# on_off_latch.net
KiCad netlist of a schematic drawn in EAGLE
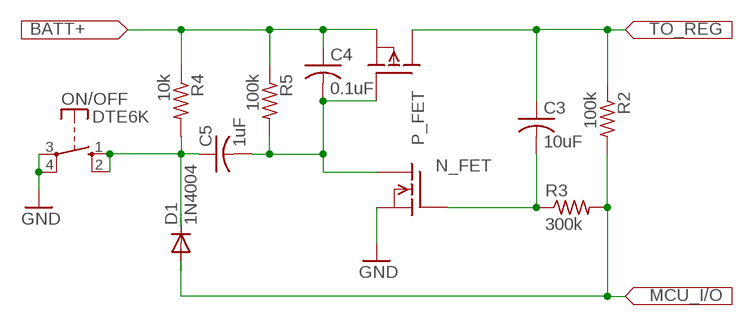
[diagram p0: schematic, sheet 1]

(export (version "E")
  (design (tool "Eeschema 10.0.6"))
  (components
    (comp (ref "C3")
      (value "10uF")
      (footprint "eagle-import:C050-024X044")
      (libsource (lib "eagle-import") (part "C-US050-024X044"))
    )
    (comp (ref "C4")
      (value "0.1uF")
      (footprint "eagle-import:C050-024X044")
      (libsource (lib "eagle-import") (part "C-US050-024X044"))
    )
    (comp (ref "C5")
      (value "1uF")
      (footprint "eagle-import:C050-024X044")
      (libsource (lib "eagle-import") (part "C-US050-024X044"))
    )
    (comp (ref "D1")
      (value "1N4004")
      (footprint "eagle-import:DO41-10")
      (libsource (lib "eagle-import") (part "1N4004"))
    )
    (comp (ref "N_FET")
      (value "BSS101")
      (footprint "eagle-import:TO92")
      (libsource (lib "eagle-import") (part "BSS101"))
    )
    (comp (ref "ON/OFF")
      (value "DTE6K")
      (footprint "eagle-import:DTE6K")
      (libsource (lib "eagle-import") (part "DTE6K"))
    )
    (comp (ref "P_FET")
      (value "BSS92")
      (footprint "eagle-import:TO92")
      (libsource (lib "eagle-import") (part "BSS92"))
    )
    (comp (ref "R2")
      (value "100k")
      (footprint "eagle-import:R0805")
      (libsource (lib "eagle-import") (part "R-US_R0805"))
    )
    (comp (ref "R3")
      (value "300k")
      (footprint "eagle-import:R0805")
      (libsource (lib "eagle-import") (part "R-US_R0805"))
    )
    (comp (ref "R4")
      (value "10k")
      (footprint "eagle-import:R0805")
      (libsource (lib "eagle-import") (part "R-US_R0805"))
    )
    (comp (ref "R5")
      (value "100k")
      (footprint "eagle-import:R0805")
      (libsource (lib "eagle-import") (part "R-US_R0805"))
    )
  )
  (nets
    (net (code "1") (name "GND") (class "Default")
      (node (ref "N_FET") (pin "1") (pinfunction "S_1") (pintype "passive"))
      (node (ref "ON/OFF") (pin "3") (pinfunction "P_3") (pintype "passive"))
      (node (ref "ON/OFF") (pin "4") (pinfunction "P_4") (pintype "passive"))
    )
    (net (code "2") (name "Net-(C5-Pad1)") (class "Default")
      (node (ref "C5") (pin "1") (pinfunction "1_1") (pintype "passive"))
      (node (ref "D1") (pin "C") (pinfunction "C_C") (pintype "passive"))
      (node (ref "ON/OFF") (pin "1") (pinfunction "S_1") (pintype "passive"))
      (node (ref "ON/OFF") (pin "2") (pinfunction "S_2") (pintype "passive"))
      (node (ref "R4") (pin "2") (pinfunction "2_2") (pintype "passive"))
    )
    (net (code "3") (name "Net-(D1-PadA)") (class "Default")
      (node (ref "D1") (pin "A") (pinfunction "A_A") (pintype "passive"))
      (node (ref "R2") (pin "2") (pinfunction "2_2") (pintype "passive"))
      (node (ref "R3") (pin "2") (pinfunction "2_2") (pintype "passive"))
    )
    (net (code "4") (name "Net-(N_FET-D)") (class "Default")
      (node (ref "C4") (pin "2") (pinfunction "2_2") (pintype "passive"))
      (node (ref "C5") (pin "2") (pinfunction "2_2") (pintype "passive"))
      (node (ref "N_FET") (pin "3") (pinfunction "D_3") (pintype "passive"))
      (node (ref "P_FET") (pin "1") (pinfunction "G_1") (pintype "passive"))
      (node (ref "R5") (pin "2") (pinfunction "2_2") (pintype "passive"))
    )
    (net (code "5") (name "Net-(N_FET-G)") (class "Default")
      (node (ref "C3") (pin "2") (pinfunction "2_2") (pintype "passive"))
      (node (ref "N_FET") (pin "2") (pinfunction "G_2") (pintype "passive"))
      (node (ref "R3") (pin "1") (pinfunction "1_1") (pintype "passive"))
    )
    (net (code "6") (name "Net-(P_FET-D)") (class "Default")
      (node (ref "C3") (pin "1") (pinfunction "1_1") (pintype "passive"))
      (node (ref "P_FET") (pin "2") (pinfunction "D_2") (pintype "passive"))
      (node (ref "R2") (pin "1") (pinfunction "1_1") (pintype "passive"))
    )
    (net (code "7") (name "Net-(P_FET-S)") (class "Default")
      (node (ref "C4") (pin "1") (pinfunction "1_1") (pintype "passive"))
      (node (ref "P_FET") (pin "3") (pinfunction "S_3") (pintype "passive"))
      (node (ref "R4") (pin "1") (pinfunction "1_1") (pintype "passive"))
      (node (ref "R5") (pin "1") (pinfunction "1_1") (pintype "passive"))
    )
  )
)
